# eth_ksz8567r_switch.net
KiCad netlist of a schematic drawn in Altium Designer
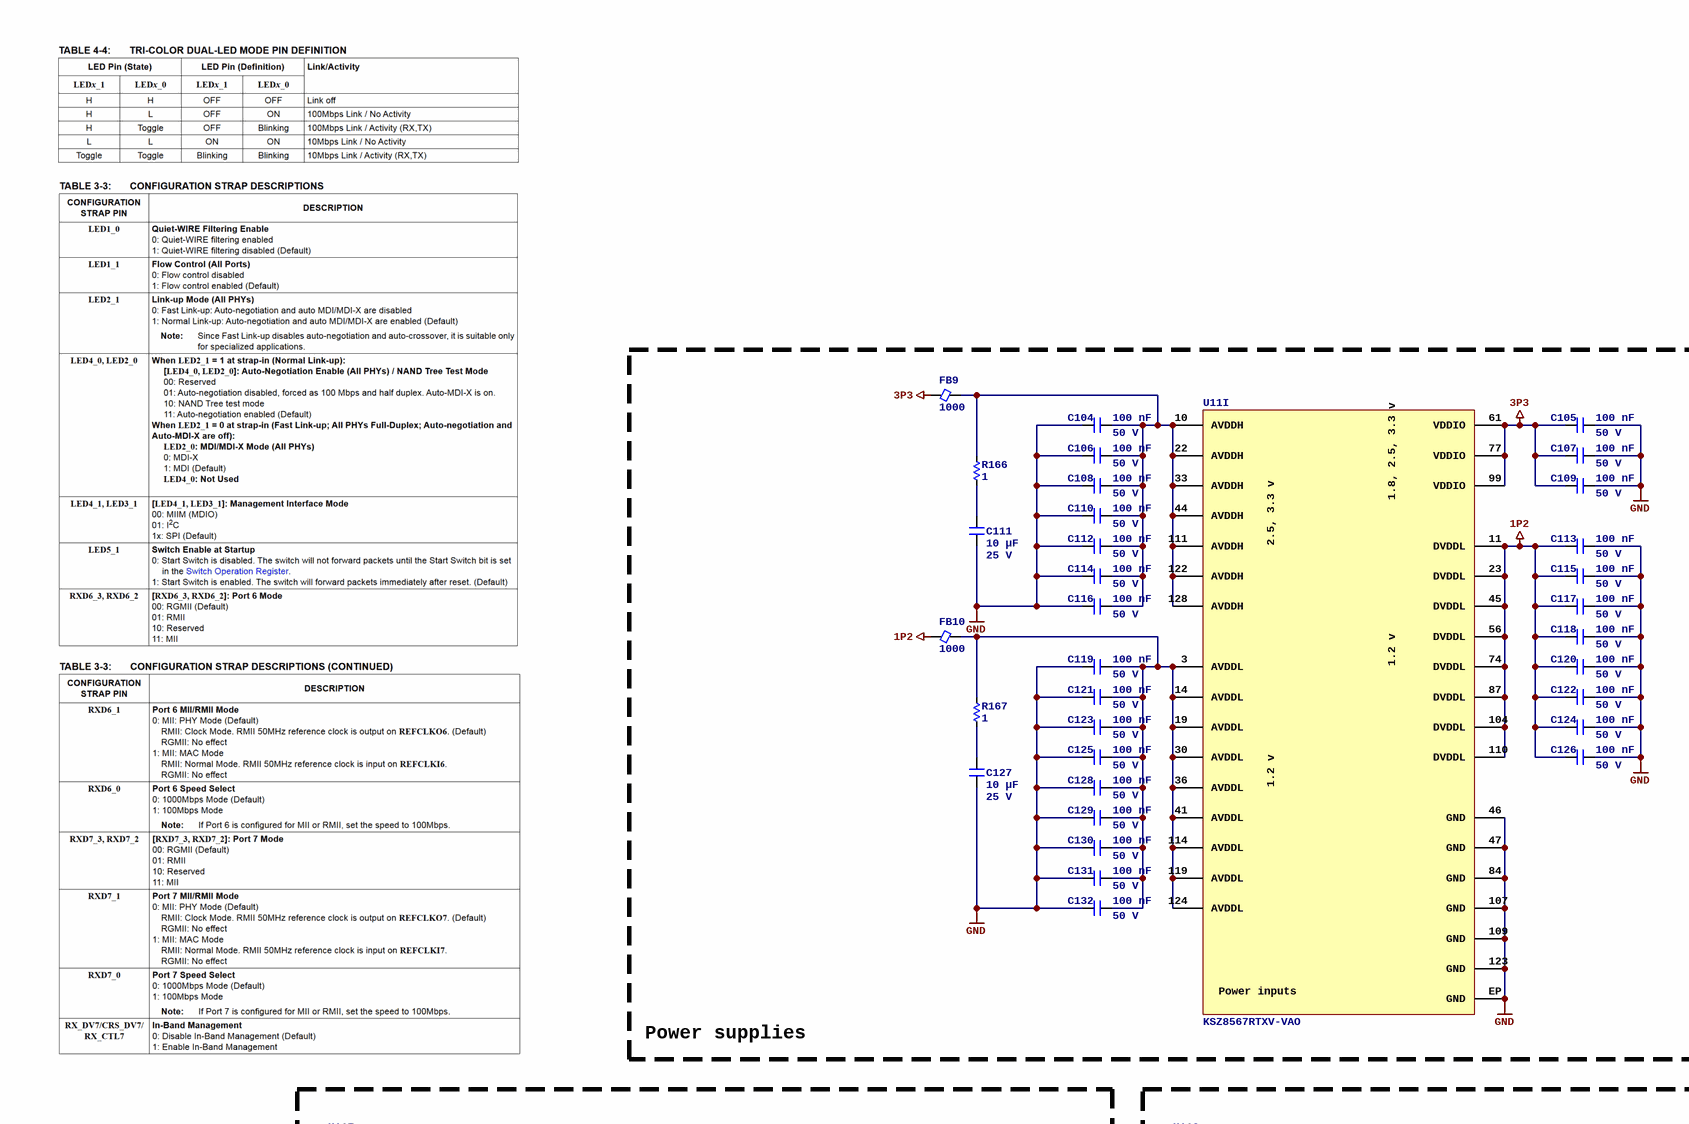
[diagram p0: eth_ksz8567r_switch.SchDoc, top left]
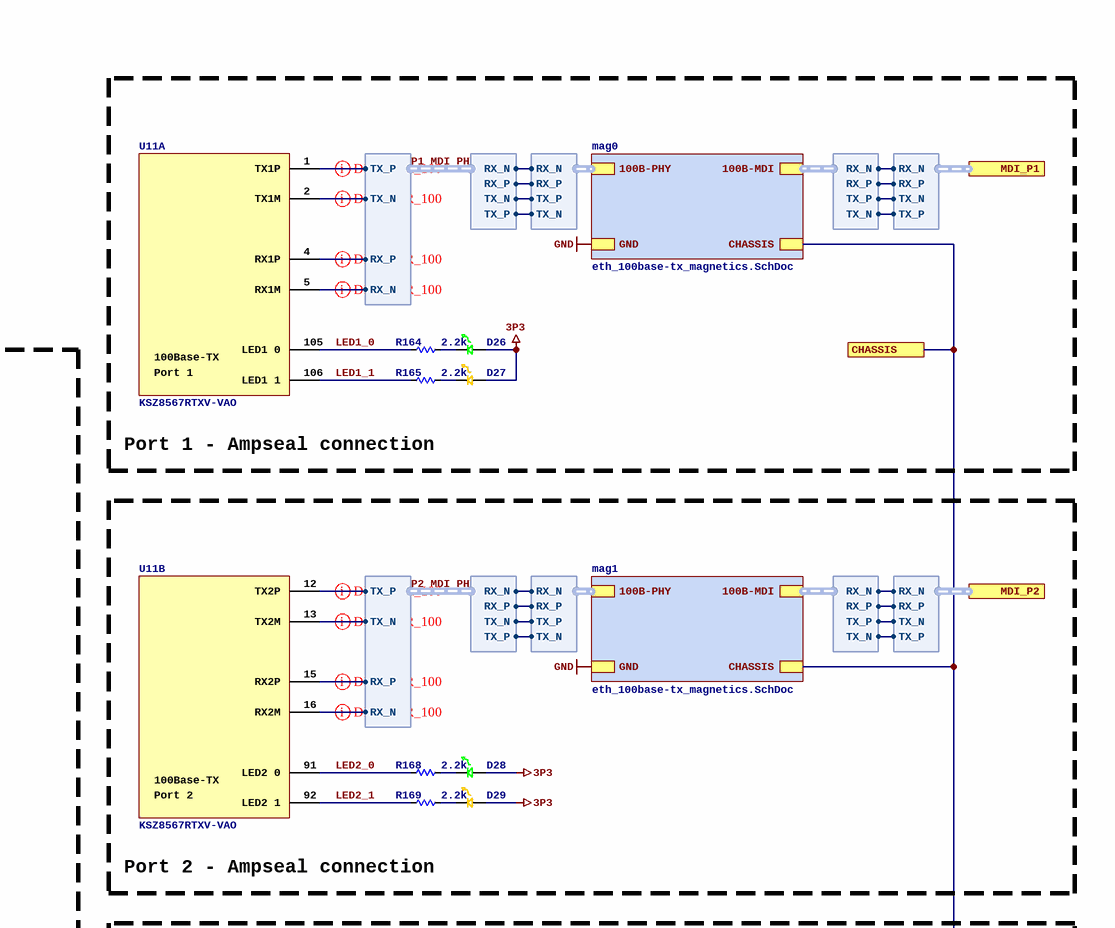
[diagram p1: eth_ksz8567r_switch.SchDoc, top right]
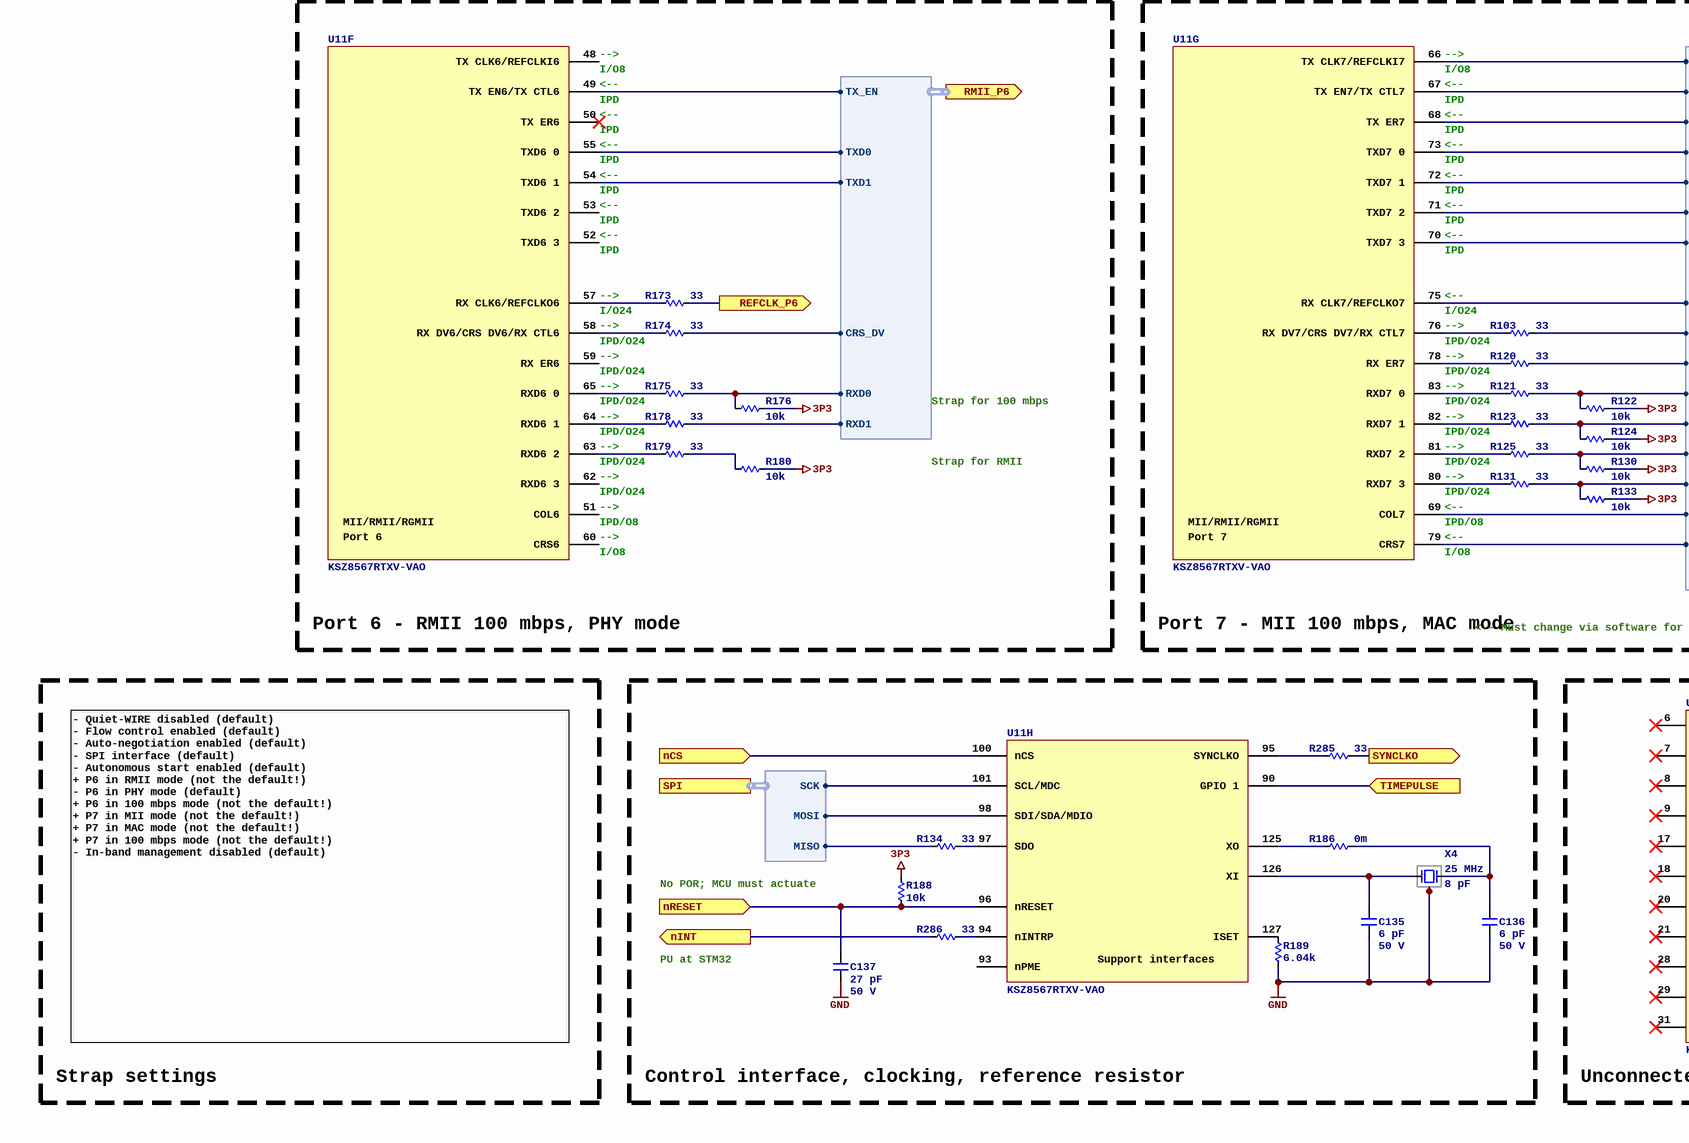
[diagram p2: eth_ksz8567r_switch.SchDoc, bottom left]
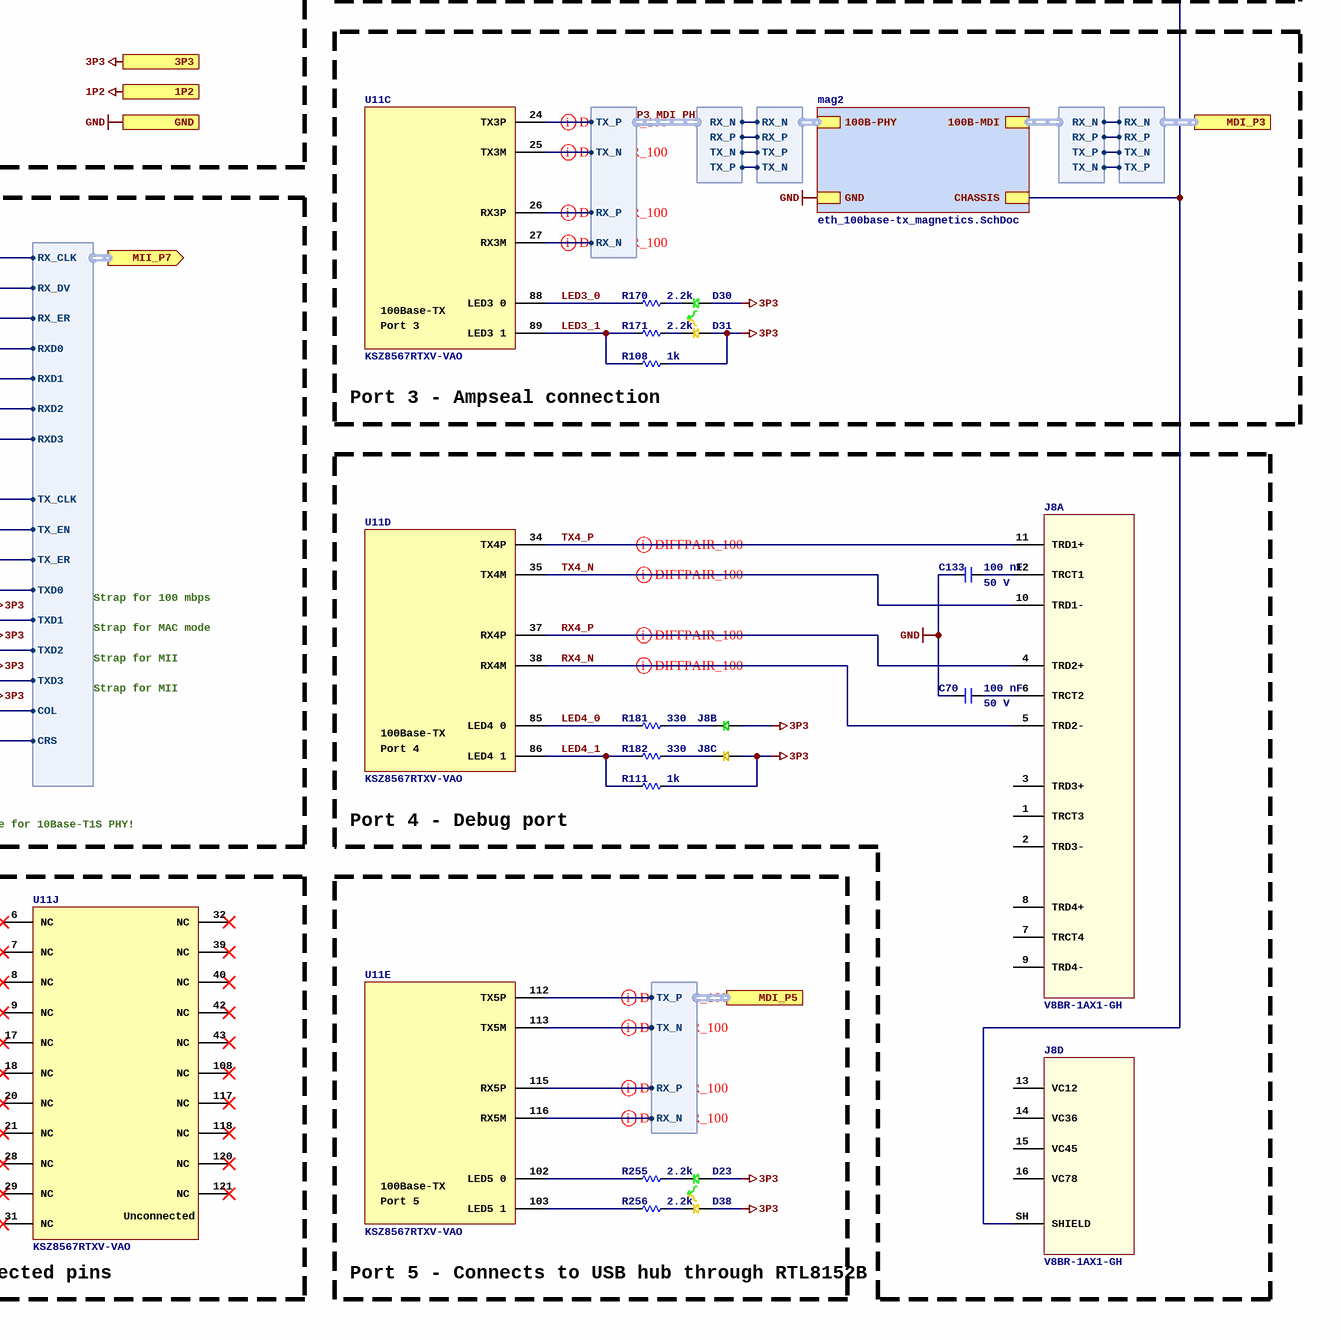
[diagram p3: eth_ksz8567r_switch.SchDoc, bottom right]

(export (version "E")
  (design (tool "Eeschema 10.0.6"))
  (components
    (comp (ref "C70")
      (value "CL05B104KB54PNC")
      (footprint "C0402")
      (fields
        (field (name "CAPACITANCE") "100 nF")
        (field (name "MANUFACTURER") "Samsung Electro-Mechanics")
        (field (name "VOLTAGE RATING") "50 V")
      )
      (libsource (lib "database") (part "__template_cap"))
    )
    (comp (ref "C104")
      (value "CL05B104KB54PNC")
      (footprint "C0402")
      (fields
        (field (name "CAPACITANCE") "100 nF")
        (field (name "MANUFACTURER") "Samsung Electro-Mechanics")
        (field (name "VOLTAGE RATING") "50 V")
      )
      (libsource (lib "database") (part "__template_cap"))
    )
    (comp (ref "C105")
      (value "CL05B104KB54PNC")
      (footprint "C0402")
      (fields
        (field (name "CAPACITANCE") "100 nF")
        (field (name "MANUFACTURER") "Samsung Electro-Mechanics")
        (field (name "VOLTAGE RATING") "50 V")
      )
      (libsource (lib "database") (part "__template_cap"))
    )
    (comp (ref "C106")
      (value "CL05B104KB54PNC")
      (footprint "C0402")
      (fields
        (field (name "CAPACITANCE") "100 nF")
        (field (name "MANUFACTURER") "Samsung Electro-Mechanics")
        (field (name "VOLTAGE RATING") "50 V")
      )
      (libsource (lib "database") (part "__template_cap"))
    )
    (comp (ref "C107")
      (value "CL05B104KB54PNC")
      (footprint "C0402")
      (fields
        (field (name "CAPACITANCE") "100 nF")
        (field (name "MANUFACTURER") "Samsung Electro-Mechanics")
        (field (name "VOLTAGE RATING") "50 V")
      )
      (libsource (lib "database") (part "__template_cap"))
    )
    (comp (ref "C108")
      (value "CL05B104KB54PNC")
      (footprint "C0402")
      (fields
        (field (name "CAPACITANCE") "100 nF")
        (field (name "MANUFACTURER") "Samsung Electro-Mechanics")
        (field (name "VOLTAGE RATING") "50 V")
      )
      (libsource (lib "database") (part "__template_cap"))
    )
    (comp (ref "C109")
      (value "CL05B104KB54PNC")
      (footprint "C0402")
      (fields
        (field (name "CAPACITANCE") "100 nF")
        (field (name "MANUFACTURER") "Samsung Electro-Mechanics")
        (field (name "VOLTAGE RATING") "50 V")
      )
      (libsource (lib "database") (part "__template_cap"))
    )
    (comp (ref "C110")
      (value "CL05B104KB54PNC")
      (footprint "C0402")
      (fields
        (field (name "CAPACITANCE") "100 nF")
        (field (name "MANUFACTURER") "Samsung Electro-Mechanics")
        (field (name "VOLTAGE RATING") "50 V")
      )
      (libsource (lib "database") (part "__template_cap"))
    )
    (comp (ref "C111")
      (value "CL21B106KAYQNNE")
      (footprint "C0805")
      (fields
        (field (name "CAPACITANCE") "10 µF")
        (field (name "MANUFACTURER") "Samsung Electro-Mechanics")
        (field (name "VOLTAGE RATING") "25 V")
      )
      (libsource (lib "database") (part "__template_cap"))
    )
    (comp (ref "C112")
      (value "CL05B104KB54PNC")
      (footprint "C0402")
      (fields
        (field (name "CAPACITANCE") "100 nF")
        (field (name "MANUFACTURER") "Samsung Electro-Mechanics")
        (field (name "VOLTAGE RATING") "50 V")
      )
      (libsource (lib "database") (part "__template_cap"))
    )
    (comp (ref "C113")
      (value "CL05B104KB54PNC")
      (footprint "C0402")
      (fields
        (field (name "CAPACITANCE") "100 nF")
        (field (name "MANUFACTURER") "Samsung Electro-Mechanics")
        (field (name "VOLTAGE RATING") "50 V")
      )
      (libsource (lib "database") (part "__template_cap"))
    )
    (comp (ref "C114")
      (value "CL05B104KB54PNC")
      (footprint "C0402")
      (fields
        (field (name "CAPACITANCE") "100 nF")
        (field (name "MANUFACTURER") "Samsung Electro-Mechanics")
        (field (name "VOLTAGE RATING") "50 V")
      )
      (libsource (lib "database") (part "__template_cap"))
    )
    (comp (ref "C115")
      (value "CL05B104KB54PNC")
      (footprint "C0402")
      (fields
        (field (name "CAPACITANCE") "100 nF")
        (field (name "MANUFACTURER") "Samsung Electro-Mechanics")
        (field (name "VOLTAGE RATING") "50 V")
      )
      (libsource (lib "database") (part "__template_cap"))
    )
    (comp (ref "C116")
      (value "CL05B104KB54PNC")
      (footprint "C0402")
      (fields
        (field (name "CAPACITANCE") "100 nF")
        (field (name "MANUFACTURER") "Samsung Electro-Mechanics")
        (field (name "VOLTAGE RATING") "50 V")
      )
      (libsource (lib "database") (part "__template_cap"))
    )
    (comp (ref "C117")
      (value "CL05B104KB54PNC")
      (footprint "C0402")
      (fields
        (field (name "CAPACITANCE") "100 nF")
        (field (name "MANUFACTURER") "Samsung Electro-Mechanics")
        (field (name "VOLTAGE RATING") "50 V")
      )
      (libsource (lib "database") (part "__template_cap"))
    )
    (comp (ref "C118")
      (value "CL05B104KB54PNC")
      (footprint "C0402")
      (fields
        (field (name "CAPACITANCE") "100 nF")
        (field (name "MANUFACTURER") "Samsung Electro-Mechanics")
        (field (name "VOLTAGE RATING") "50 V")
      )
      (libsource (lib "database") (part "__template_cap"))
    )
    (comp (ref "C119")
      (value "CL05B104KB54PNC")
      (footprint "C0402")
      (fields
        (field (name "CAPACITANCE") "100 nF")
        (field (name "MANUFACTURER") "Samsung Electro-Mechanics")
        (field (name "VOLTAGE RATING") "50 V")
      )
      (libsource (lib "database") (part "__template_cap"))
    )
    (comp (ref "C120")
      (value "CL05B104KB54PNC")
      (footprint "C0402")
      (fields
        (field (name "CAPACITANCE") "100 nF")
        (field (name "MANUFACTURER") "Samsung Electro-Mechanics")
        (field (name "VOLTAGE RATING") "50 V")
      )
      (libsource (lib "database") (part "__template_cap"))
    )
    (comp (ref "C121")
      (value "CL05B104KB54PNC")
      (footprint "C0402")
      (fields
        (field (name "CAPACITANCE") "100 nF")
        (field (name "MANUFACTURER") "Samsung Electro-Mechanics")
        (field (name "VOLTAGE RATING") "50 V")
      )
      (libsource (lib "database") (part "__template_cap"))
    )
    (comp (ref "C122")
      (value "CL05B104KB54PNC")
      (footprint "C0402")
      (fields
        (field (name "CAPACITANCE") "100 nF")
        (field (name "MANUFACTURER") "Samsung Electro-Mechanics")
        (field (name "VOLTAGE RATING") "50 V")
      )
      (libsource (lib "database") (part "__template_cap"))
    )
    (comp (ref "C123")
      (value "CL05B104KB54PNC")
      (footprint "C0402")
      (fields
        (field (name "CAPACITANCE") "100 nF")
        (field (name "MANUFACTURER") "Samsung Electro-Mechanics")
        (field (name "VOLTAGE RATING") "50 V")
      )
      (libsource (lib "database") (part "__template_cap"))
    )
    (comp (ref "C124")
      (value "CL05B104KB54PNC")
      (footprint "C0402")
      (fields
        (field (name "CAPACITANCE") "100 nF")
        (field (name "MANUFACTURER") "Samsung Electro-Mechanics")
        (field (name "VOLTAGE RATING") "50 V")
      )
      (libsource (lib "database") (part "__template_cap"))
    )
    (comp (ref "C125")
      (value "CL05B104KB54PNC")
      (footprint "C0402")
      (fields
        (field (name "CAPACITANCE") "100 nF")
        (field (name "MANUFACTURER") "Samsung Electro-Mechanics")
        (field (name "VOLTAGE RATING") "50 V")
      )
      (libsource (lib "database") (part "__template_cap"))
    )
    (comp (ref "C126")
      (value "CL05B104KB54PNC")
      (footprint "C0402")
      (fields
        (field (name "CAPACITANCE") "100 nF")
        (field (name "MANUFACTURER") "Samsung Electro-Mechanics")
        (field (name "VOLTAGE RATING") "50 V")
      )
      (libsource (lib "database") (part "__template_cap"))
    )
    (comp (ref "C127")
      (value "CL21B106KAYQNNE")
      (footprint "C0805")
      (fields
        (field (name "CAPACITANCE") "10 µF")
        (field (name "MANUFACTURER") "Samsung Electro-Mechanics")
        (field (name "VOLTAGE RATING") "25 V")
      )
      (libsource (lib "database") (part "__template_cap"))
    )
    (comp (ref "C128")
      (value "CL05B104KB54PNC")
      (footprint "C0402")
      (fields
        (field (name "CAPACITANCE") "100 nF")
        (field (name "MANUFACTURER") "Samsung Electro-Mechanics")
        (field (name "VOLTAGE RATING") "50 V")
      )
      (libsource (lib "database") (part "__template_cap"))
    )
    (comp (ref "C129")
      (value "CL05B104KB54PNC")
      (footprint "C0402")
      (fields
        (field (name "CAPACITANCE") "100 nF")
        (field (name "MANUFACTURER") "Samsung Electro-Mechanics")
        (field (name "VOLTAGE RATING") "50 V")
      )
      (libsource (lib "database") (part "__template_cap"))
    )
    (comp (ref "C130")
      (value "CL05B104KB54PNC")
      (footprint "C0402")
      (fields
        (field (name "CAPACITANCE") "100 nF")
        (field (name "MANUFACTURER") "Samsung Electro-Mechanics")
        (field (name "VOLTAGE RATING") "50 V")
      )
      (libsource (lib "database") (part "__template_cap"))
    )
    (comp (ref "C131")
      (value "CL05B104KB54PNC")
      (footprint "C0402")
      (fields
        (field (name "CAPACITANCE") "100 nF")
        (field (name "MANUFACTURER") "Samsung Electro-Mechanics")
        (field (name "VOLTAGE RATING") "50 V")
      )
      (libsource (lib "database") (part "__template_cap"))
    )
    (comp (ref "C132")
      (value "CL05B104KB54PNC")
      (footprint "C0402")
      (fields
        (field (name "CAPACITANCE") "100 nF")
        (field (name "MANUFACTURER") "Samsung Electro-Mechanics")
        (field (name "VOLTAGE RATING") "50 V")
      )
      (libsource (lib "database") (part "__template_cap"))
    )
    (comp (ref "C133")
      (value "CL05B104KB54PNC")
      (footprint "C0402")
      (fields
        (field (name "CAPACITANCE") "100 nF")
        (field (name "MANUFACTURER") "Samsung Electro-Mechanics")
        (field (name "VOLTAGE RATING") "50 V")
      )
      (libsource (lib "database") (part "__template_cap"))
    )
    (comp (ref "C135")
      (value "0402CG6R0C500NT")
      (footprint "C0402")
      (fields
        (field (name "CAPACITANCE") "6 pF")
        (field (name "MANUFACTURER") "FH(Guangdong Fenghua Advanced Tech)")
        (field (name "VOLTAGE RATING") "50 V")
      )
      (libsource (lib "database") (part "__template_cap"))
    )
    (comp (ref "C136")
      (value "0402CG6R0C500NT")
      (footprint "C0402")
      (fields
        (field (name "CAPACITANCE") "6 pF")
        (field (name "MANUFACTURER") "FH(Guangdong Fenghua Advanced Tech)")
        (field (name "VOLTAGE RATING") "50 V")
      )
      (libsource (lib "database") (part "__template_cap"))
    )
    (comp (ref "C137")
      (value "0402CG270J500NT")
      (footprint "C0402")
      (fields
        (field (name "CAPACITANCE") "27 pF")
        (field (name "MANUFACTURER") "FH(Guangdong Fenghua Advanced Tech)")
        (field (name "VOLTAGE RATING") "50 V")
      )
      (libsource (lib "database") (part "__template_cap"))
    )
    (comp (ref "D23")
      (value "LTST-C190GKT")
      (footprint "LED_0603P_GREEN")
      (description "LED GREEN CLEAR 0603 SMD")
      (fields (field (name "MANUFACTURER") "Lite-On Inc"))
      (libsource (lib "") (part "__template_led_green_1"))
    )
    (comp (ref "D26")
      (value "LTST-C190GKT")
      (footprint "LED_0603P_GREEN")
      (description "LED GREEN CLEAR 0603 SMD")
      (fields (field (name "MANUFACTURER") "Lite-On Inc"))
      (libsource (lib "database") (part "__template_led_green"))
    )
    (comp (ref "D27")
      (value "LTST-C190AKT")
      (footprint "LED_0603P_AMBER")
      (description "LED AMBER CLEAR 0603 SMD")
      (fields (field (name "MANUFACTURER") "Lite-On Inc"))
      (libsource (lib "database") (part "__template_led_amber"))
    )
    (comp (ref "D28")
      (value "LTST-C190GKT")
      (footprint "LED_0603P_GREEN")
      (description "LED GREEN CLEAR 0603 SMD")
      (fields (field (name "MANUFACTURER") "Lite-On Inc"))
      (libsource (lib "database") (part "__template_led_green"))
    )
    (comp (ref "D29")
      (value "LTST-C190AKT")
      (footprint "LED_0603P_AMBER")
      (description "LED AMBER CLEAR 0603 SMD")
      (fields (field (name "MANUFACTURER") "Lite-On Inc"))
      (libsource (lib "database") (part "__template_led_amber"))
    )
    (comp (ref "D30")
      (value "LTST-C190GKT")
      (footprint "LED_0603P_GREEN")
      (description "LED GREEN CLEAR 0603 SMD")
      (fields (field (name "MANUFACTURER") "Lite-On Inc"))
      (libsource (lib "") (part "__template_led_green_1"))
    )
    (comp (ref "D31")
      (value "LTST-C190AKT")
      (footprint "LED_0603P_AMBER")
      (description "LED AMBER CLEAR 0603 SMD")
      (fields (field (name "MANUFACTURER") "Lite-On Inc"))
      (libsource (lib "database") (part "__template_led_amber"))
    )
    (comp (ref "D38")
      (value "LTST-C190AKT")
      (footprint "LED_0603P_AMBER")
      (description "LED AMBER CLEAR 0603 SMD")
      (fields (field (name "MANUFACTURER") "Lite-On Inc"))
      (libsource (lib "database") (part "__template_led_amber"))
    )
    (comp (ref "FB9")
      (value "MGGB2012M600HT-LF")
      (footprint "FB0805")
      (fields (field (name "MANUFACTURER") "microgate") (field (name "CURRENT RATING (MA)") "1000"))
      (libsource (lib "database") (part "__template_fb"))
    )
    (comp (ref "FB10")
      (value "MGGB2012M600HT-LF")
      (footprint "FB0805")
      (fields (field (name "MANUFACTURER") "microgate") (field (name "CURRENT RATING (MA)") "1000"))
      (libsource (lib "database") (part "__template_fb"))
    )
    (comp (ref "J8")
      (value "V8BR-1AX1-GH")
      (footprint "BELFUSE_V8BR-1AX1-GH")
      (description "Conn RJ-45 F 8 POS 1.02mm Solder ST Thru-Hole 20 Terminal 1 Port Tray")
      (fields (field (name "MANUFACTURER") "Bel"))
      (libsource (lib "") (part "V8BR-1AX1-GH_1"))
    )
    (comp (ref "R103")
      (value "33")
      (footprint "R0402")
      (fields
        (field (name "TOLERANCE") "1%")
        (field (name "MANUFACTURER PART NUMBER") "0402WGF330JTCE")
        (field (name "MANUFACTURER") "UNI-ROYAL(Uniroyal Elec)")
      )
      (libsource (lib "database") (part "__template_resistor"))
    )
    (comp (ref "R108")
      (value "1k")
      (footprint "R0402")
      (fields
        (field (name "TOLERANCE") "1%")
        (field (name "MANUFACTURER PART NUMBER") "0402WGF1001TCE")
        (field (name "MANUFACTURER") "UNI-ROYAL(Uniroyal Elec)")
      )
      (libsource (lib "database") (part "__template_resistor"))
    )
    (comp (ref "R111")
      (value "1k")
      (footprint "R0402")
      (fields
        (field (name "TOLERANCE") "1%")
        (field (name "MANUFACTURER PART NUMBER") "0402WGF1001TCE")
        (field (name "MANUFACTURER") "UNI-ROYAL(Uniroyal Elec)")
      )
      (libsource (lib "database") (part "__template_resistor"))
    )
    (comp (ref "R120")
      (value "33")
      (footprint "R0402")
      (fields
        (field (name "TOLERANCE") "1%")
        (field (name "MANUFACTURER PART NUMBER") "0402WGF330JTCE")
        (field (name "MANUFACTURER") "UNI-ROYAL(Uniroyal Elec)")
      )
      (libsource (lib "database") (part "__template_resistor"))
    )
    (comp (ref "R121")
      (value "33")
      (footprint "R0402")
      (fields
        (field (name "TOLERANCE") "1%")
        (field (name "MANUFACTURER PART NUMBER") "0402WGF330JTCE")
        (field (name "MANUFACTURER") "UNI-ROYAL(Uniroyal Elec)")
      )
      (libsource (lib "database") (part "__template_resistor"))
    )
    (comp (ref "R122")
      (value "10k")
      (footprint "R0402")
      (fields
        (field (name "TOLERANCE") "1%")
        (field (name "MANUFACTURER PART NUMBER") "0402WGF1002TCE")
        (field (name "MANUFACTURER") "UNI-ROYAL(Uniroyal Elec)")
      )
      (libsource (lib "database") (part "__template_resistor"))
    )
    (comp (ref "R123")
      (value "33")
      (footprint "R0402")
      (fields
        (field (name "TOLERANCE") "1%")
        (field (name "MANUFACTURER PART NUMBER") "0402WGF330JTCE")
        (field (name "MANUFACTURER") "UNI-ROYAL(Uniroyal Elec)")
      )
      (libsource (lib "database") (part "__template_resistor"))
    )
    (comp (ref "R124")
      (value "10k")
      (footprint "R0402")
      (fields
        (field (name "TOLERANCE") "1%")
        (field (name "MANUFACTURER PART NUMBER") "0402WGF1002TCE")
        (field (name "MANUFACTURER") "UNI-ROYAL(Uniroyal Elec)")
      )
      (libsource (lib "database") (part "__template_resistor"))
    )
    (comp (ref "R125")
      (value "33")
      (footprint "R0402")
      (fields
        (field (name "TOLERANCE") "1%")
        (field (name "MANUFACTURER PART NUMBER") "0402WGF330JTCE")
        (field (name "MANUFACTURER") "UNI-ROYAL(Uniroyal Elec)")
      )
      (libsource (lib "database") (part "__template_resistor"))
    )
    (comp (ref "R130")
      (value "10k")
      (footprint "R0402")
      (fields
        (field (name "TOLERANCE") "1%")
        (field (name "MANUFACTURER PART NUMBER") "0402WGF1002TCE")
        (field (name "MANUFACTURER") "UNI-ROYAL(Uniroyal Elec)")
      )
      (libsource (lib "database") (part "__template_resistor"))
    )
    (comp (ref "R131")
      (value "33")
      (footprint "R0402")
      (fields
        (field (name "TOLERANCE") "1%")
        (field (name "MANUFACTURER PART NUMBER") "0402WGF330JTCE")
        (field (name "MANUFACTURER") "UNI-ROYAL(Uniroyal Elec)")
      )
      (libsource (lib "database") (part "__template_resistor"))
    )
    (comp (ref "R133")
      (value "10k")
      (footprint "R0402")
      (fields
        (field (name "TOLERANCE") "1%")
        (field (name "MANUFACTURER PART NUMBER") "0402WGF1002TCE")
        (field (name "MANUFACTURER") "UNI-ROYAL(Uniroyal Elec)")
      )
      (libsource (lib "database") (part "__template_resistor"))
    )
    (comp (ref "R134")
      (value "33")
      (footprint "R0402")
      (fields
        (field (name "TOLERANCE") "1%")
        (field (name "MANUFACTURER PART NUMBER") "0402WGF330JTCE")
        (field (name "MANUFACTURER") "UNI-ROYAL(Uniroyal Elec)")
      )
      (libsource (lib "database") (part "__template_resistor"))
    )
    (comp (ref "R164")
      (value "2.2k")
      (footprint "R0402")
      (fields
        (field (name "TOLERANCE") "1%")
        (field (name "MANUFACTURER PART NUMBER") "0402WGF2201TCE")
        (field (name "MANUFACTURER") "UNI-ROYAL(Uniroyal Elec)")
      )
      (libsource (lib "database") (part "__template_resistor"))
    )
    (comp (ref "R165")
      (value "2.2k")
      (footprint "R0402")
      (fields
        (field (name "TOLERANCE") "1%")
        (field (name "MANUFACTURER PART NUMBER") "0402WGF2201TCE")
        (field (name "MANUFACTURER") "UNI-ROYAL(Uniroyal Elec)")
      )
      (libsource (lib "database") (part "__template_resistor"))
    )
    (comp (ref "R166")
      (value "1")
      (footprint "R0402")
      (fields
        (field (name "TOLERANCE") "1%")
        (field (name "MANUFACTURER PART NUMBER") "CRCW04021R00FKED")
        (field (name "MANUFACTURER") "Vishay Intertech")
      )
      (libsource (lib "database") (part "__template_resistor"))
    )
    (comp (ref "R167")
      (value "1")
      (footprint "R0402")
      (fields
        (field (name "TOLERANCE") "1%")
        (field (name "MANUFACTURER PART NUMBER") "CRCW04021R00FKED")
        (field (name "MANUFACTURER") "Vishay Intertech")
      )
      (libsource (lib "database") (part "__template_resistor"))
    )
    (comp (ref "R168")
      (value "2.2k")
      (footprint "R0402")
      (fields
        (field (name "TOLERANCE") "1%")
        (field (name "MANUFACTURER PART NUMBER") "0402WGF2201TCE")
        (field (name "MANUFACTURER") "UNI-ROYAL(Uniroyal Elec)")
      )
      (libsource (lib "database") (part "__template_resistor"))
    )
    (comp (ref "R169")
      (value "2.2k")
      (footprint "R0402")
      (fields
        (field (name "TOLERANCE") "1%")
        (field (name "MANUFACTURER PART NUMBER") "0402WGF2201TCE")
        (field (name "MANUFACTURER") "UNI-ROYAL(Uniroyal Elec)")
      )
      (libsource (lib "database") (part "__template_resistor"))
    )
    (comp (ref "R170")
      (value "2.2k")
      (footprint "R0402")
      (fields
        (field (name "TOLERANCE") "1%")
        (field (name "MANUFACTURER PART NUMBER") "0402WGF2201TCE")
        (field (name "MANUFACTURER") "UNI-ROYAL(Uniroyal Elec)")
      )
      (libsource (lib "database") (part "__template_resistor"))
    )
    (comp (ref "R171")
      (value "2.2k")
      (footprint "R0402")
      (fields
        (field (name "TOLERANCE") "1%")
        (field (name "MANUFACTURER PART NUMBER") "0402WGF2201TCE")
        (field (name "MANUFACTURER") "UNI-ROYAL(Uniroyal Elec)")
      )
      (libsource (lib "database") (part "__template_resistor"))
    )
    (comp (ref "R173")
      (value "33")
      (footprint "R0402")
      (fields
        (field (name "TOLERANCE") "1%")
        (field (name "MANUFACTURER PART NUMBER") "0402WGF330JTCE")
        (field (name "MANUFACTURER") "UNI-ROYAL(Uniroyal Elec)")
      )
      (libsource (lib "database") (part "__template_resistor"))
    )
    (comp (ref "R174")
      (value "33")
      (footprint "R0402")
      (fields
        (field (name "TOLERANCE") "1%")
        (field (name "MANUFACTURER PART NUMBER") "0402WGF330JTCE")
        (field (name "MANUFACTURER") "UNI-ROYAL(Uniroyal Elec)")
      )
      (libsource (lib "database") (part "__template_resistor"))
    )
    (comp (ref "R175")
      (value "33")
      (footprint "R0402")
      (fields
        (field (name "TOLERANCE") "1%")
        (field (name "MANUFACTURER PART NUMBER") "0402WGF330JTCE")
        (field (name "MANUFACTURER") "UNI-ROYAL(Uniroyal Elec)")
      )
      (libsource (lib "database") (part "__template_resistor"))
    )
    (comp (ref "R176")
      (value "10k")
      (footprint "R0402")
      (fields
        (field (name "TOLERANCE") "1%")
        (field (name "MANUFACTURER PART NUMBER") "0402WGF1002TCE")
        (field (name "MANUFACTURER") "UNI-ROYAL(Uniroyal Elec)")
      )
      (libsource (lib "database") (part "__template_resistor"))
    )
    (comp (ref "R178")
      (value "33")
      (footprint "R0402")
      (fields
        (field (name "TOLERANCE") "1%")
        (field (name "MANUFACTURER PART NUMBER") "0402WGF330JTCE")
        (field (name "MANUFACTURER") "UNI-ROYAL(Uniroyal Elec)")
      )
      (libsource (lib "database") (part "__template_resistor"))
    )
    (comp (ref "R179")
      (value "33")
      (footprint "R0402")
      (fields
        (field (name "TOLERANCE") "1%")
        (field (name "MANUFACTURER PART NUMBER") "0402WGF330JTCE")
        (field (name "MANUFACTURER") "UNI-ROYAL(Uniroyal Elec)")
      )
      (libsource (lib "database") (part "__template_resistor"))
    )
    (comp (ref "R180")
      (value "10k")
      (footprint "R0402")
      (fields
        (field (name "TOLERANCE") "1%")
        (field (name "MANUFACTURER PART NUMBER") "0402WGF1002TCE")
        (field (name "MANUFACTURER") "UNI-ROYAL(Uniroyal Elec)")
      )
      (libsource (lib "database") (part "__template_resistor"))
    )
    (comp (ref "R181")
      (value "330")
      (footprint "R0402")
      (fields
        (field (name "TOLERANCE") "1%")
        (field (name "MANUFACTURER PART NUMBER") "0402WGF3300TCE")
        (field (name "MANUFACTURER") "UNI-ROYAL(Uniroyal Elec)")
      )
      (libsource (lib "database") (part "__template_resistor"))
    )
    (comp (ref "R182")
      (value "330")
      (footprint "R0402")
      (fields
        (field (name "TOLERANCE") "1%")
        (field (name "MANUFACTURER PART NUMBER") "0402WGF3300TCE")
        (field (name "MANUFACTURER") "UNI-ROYAL(Uniroyal Elec)")
      )
      (libsource (lib "database") (part "__template_resistor"))
    )
    (comp (ref "R186")
      (value "0m")
      (footprint "R0402")
      (fields
        (field (name "MANUFACTURER PART NUMBER") "0402WGF0000TCE")
        (field (name "MANUFACTURER") "UNI-ROYAL(Uniroyal Elec)")
      )
      (libsource (lib "database") (part "__template_resistor"))
    )
    (comp (ref "R188")
      (value "10k")
      (footprint "R0402")
      (fields
        (field (name "TOLERANCE") "1%")
        (field (name "MANUFACTURER PART NUMBER") "0402WGF1002TCE")
        (field (name "MANUFACTURER") "UNI-ROYAL(Uniroyal Elec)")
      )
      (libsource (lib "database") (part "__template_resistor"))
    )
    (comp (ref "R189")
      (value "6.04k")
      (footprint "R0402")
      (fields
        (field (name "TOLERANCE") "1%")
        (field (name "MANUFACTURER PART NUMBER") "0402WGF6041TCE")
        (field (name "MANUFACTURER") "UNI-ROYAL(Uniroyal Elec)")
      )
      (libsource (lib "database") (part "__template_resistor"))
    )
    (comp (ref "R255")
      (value "2.2k")
      (footprint "R0402")
      (fields
        (field (name "TOLERANCE") "1%")
        (field (name "MANUFACTURER PART NUMBER") "0402WGF2201TCE")
        (field (name "MANUFACTURER") "UNI-ROYAL(Uniroyal Elec)")
      )
      (libsource (lib "database") (part "__template_resistor"))
    )
    (comp (ref "R256")
      (value "2.2k")
      (footprint "R0402")
      (fields
        (field (name "TOLERANCE") "1%")
        (field (name "MANUFACTURER PART NUMBER") "0402WGF2201TCE")
        (field (name "MANUFACTURER") "UNI-ROYAL(Uniroyal Elec)")
      )
      (libsource (lib "database") (part "__template_resistor"))
    )
    (comp (ref "R285")
      (value "33")
      (footprint "R0402")
      (fields
        (field (name "TOLERANCE") "1%")
        (field (name "MANUFACTURER PART NUMBER") "0402WGF330JTCE")
        (field (name "MANUFACTURER") "UNI-ROYAL(Uniroyal Elec)")
      )
      (libsource (lib "database") (part "__template_resistor"))
    )
    (comp (ref "R286")
      (value "33")
      (footprint "R0402")
      (fields
        (field (name "TOLERANCE") "1%")
        (field (name "MANUFACTURER PART NUMBER") "0402WGF330JTCE")
        (field (name "MANUFACTURER") "UNI-ROYAL(Uniroyal Elec)")
      )
      (libsource (lib "database") (part "__template_resistor"))
    )
    (comp (ref "U11")
      (value "KSZ8567RTXV-VAO")
      (footprint "MICROCHIP_C04-418B_128TQFP_14X14_10X10EP")
      (description "Automotive Ethernet Switch 7 Port 10Mbps/100Mbps 128-Pin TQFP EP Tray")
      (fields (field (name "MANUFACTURER") "Microchip"))
      (libsource (lib "database") (part "KSZ8567RTXV-VAO"))
    )
    (comp (ref "X4")
      (value "ABM11W-25.0000MHZ-8-D1X-T3")
      (footprint "4_SMD_2.0X1.6MM")
      (description "25 MHz ±10ppm Crystal 8pF 50 Ohms 4-SMD, No Lead")
      (fields
        (field (name "MANUFACTURER") "Abracon LLC")
        (field (name "FREQUENCY") "25 MHz")
        (field (name "CAPACITANCE") "8 pF")
      )
      (libsource (lib "database") (part "__template_crystal_4pin"))
    )
  )
  (nets
    (net (code "8") (name "/CHASSIS") (class "Default")
      (node (ref "J8") (pin "SH") (pinfunction "SHIELD_SH") (pintype "passive"))
    )
    (net (code "9") (name "/COL") (class "Default")
      (node (ref "U11") (pin "69") (pinfunction "COL7_69") (pintype "passive"))
    )
    (net (code "10") (name "/CRS") (class "Default")
      (node (ref "U11") (pin "79") (pinfunction "CRS7_79") (pintype "passive"))
    )
    (net (code "11") (name "/CRS_DV") (class "Default") (node (ref "R174") (pin "1") (pintype "passive")))
    (net (code "12") (name "/LED1_0") (class "Default")
      (node (ref "R164") (pin "2") (pintype "passive"))
      (node (ref "U11") (pin "105") (pinfunction "LED1_0_105") (pintype "passive"))
    )
    (net (code "13") (name "/LED1_1") (class "Default")
      (node (ref "R165") (pin "2") (pintype "passive"))
      (node (ref "U11") (pin "106") (pinfunction "LED1_1_106") (pintype "passive"))
    )
    (net (code "14") (name "/LED2_0") (class "Default")
      (node (ref "R168") (pin "2") (pintype "passive"))
      (node (ref "U11") (pin "91") (pinfunction "LED2_0_91") (pintype "passive"))
    )
    (net (code "15") (name "/LED2_1") (class "Default")
      (node (ref "R169") (pin "2") (pintype "passive"))
      (node (ref "U11") (pin "92") (pinfunction "LED2_1_92") (pintype "passive"))
    )
    (net (code "16") (name "/LED3_0") (class "Default")
      (node (ref "R170") (pin "2") (pintype "passive"))
      (node (ref "U11") (pin "88") (pinfunction "LED3_0_88") (pintype "passive"))
    )
    (net (code "17") (name "/LED3_1") (class "Default")
      (node (ref "R108") (pin "2") (pintype "passive"))
      (node (ref "R171") (pin "2") (pintype "passive"))
      (node (ref "U11") (pin "89") (pinfunction "LED3_1_89") (pintype "passive"))
    )
    (net (code "18") (name "/LED4_0") (class "Default")
      (node (ref "R181") (pin "1") (pintype "passive"))
      (node (ref "U11") (pin "85") (pinfunction "LED4_0_85") (pintype "passive"))
    )
    (net (code "19") (name "/LED4_1") (class "Default")
      (node (ref "R111") (pin "2") (pintype "passive"))
      (node (ref "R182") (pin "1") (pintype "passive"))
      (node (ref "U11") (pin "86") (pinfunction "LED4_1_86") (pintype "passive"))
    )
    (net (code "20") (name "/MISO") (class "Default") (node (ref "R134") (pin "2") (pintype "passive")))
    (net (code "21") (name "/MOSI") (class "Default")
      (node (ref "U11") (pin "98") (pinfunction "SDI/SDA/MDIO_98") (pintype "passive"))
    )
    (net (code "25") (name "/REFCLK_P6") (class "Default") (node (ref "R173") (pin "1") (pintype "passive")))
    (net (code "26") (name "/RX4_N") (class "Default")
      (node (ref "J8") (pin "5") (pinfunction "TRD2-_5") (pintype "passive"))
      (node (ref "U11") (pin "38") (pinfunction "RX4M_38") (pintype "passive"))
    )
    (net (code "27") (name "/RX4_P") (class "Default")
      (node (ref "J8") (pin "4") (pinfunction "TRD2+_4") (pintype "passive"))
      (node (ref "U11") (pin "37") (pinfunction "RX4P_37") (pintype "passive"))
    )
    (net (code "28") (name "/RXD2") (class "Default")
      (node (ref "U11") (pin "71") (pinfunction "TXD7_2_71") (pintype "passive"))
    )
    (net (code "29") (name "/RXD3") (class "Default")
      (node (ref "U11") (pin "70") (pinfunction "TXD7_3_70") (pintype "passive"))
    )
    (net (code "30") (name "/RX_CLK") (class "Default")
      (node (ref "U11") (pin "66") (pinfunction "TX_CLK7/REFCLKI7_66") (pintype "passive"))
    )
    (net (code "31") (name "/RX_DV") (class "Default")
      (node (ref "U11") (pin "67") (pinfunction "TX_EN7/TX_CTL7_67") (pintype "passive"))
    )
    (net (code "32") (name "/RX_ER") (class "Default")
      (node (ref "U11") (pin "68") (pinfunction "TX_ER7_68") (pintype "passive"))
    )
    (net (code "33") (name "/SCK") (class "Default")
      (node (ref "U11") (pin "101") (pinfunction "SCL/MDC_101") (pintype "passive"))
    )
    (net (code "34") (name "/SYNCLKO") (class "Default") (node (ref "R285") (pin "1") (pintype "passive")))
    (net (code "35") (name "/TIMEPULSE") (class "Default")
      (node (ref "U11") (pin "90") (pinfunction "GPIO_1_90") (pintype "passive"))
    )
    (net (code "36") (name "/TX4_N") (class "Default")
      (node (ref "J8") (pin "10") (pinfunction "TRD1-_10") (pintype "passive"))
      (node (ref "U11") (pin "35") (pinfunction "TX4M_35") (pintype "passive"))
    )
    (net (code "37") (name "/TX4_P") (class "Default")
      (node (ref "J8") (pin "11") (pinfunction "TRD1+_11") (pintype "passive"))
      (node (ref "U11") (pin "34") (pinfunction "TX4P_34") (pintype "passive"))
    )
    (net (code "38") (name "/TXD2") (class "Default")
      (node (ref "R125") (pin "1") (pintype "passive"))
      (node (ref "R130") (pin "2") (pintype "passive"))
    )
    (net (code "39") (name "/TXD3") (class "Default")
      (node (ref "R131") (pin "1") (pintype "passive"))
      (node (ref "R133") (pin "2") (pintype "passive"))
    )
    (net (code "40") (name "/TX_CLK") (class "Default")
      (node (ref "U11") (pin "75") (pinfunction "RX_CLK7/REFCLKO7_75") (pintype "passive"))
    )
    (net (code "41") (name "/TX_ER") (class "Default") (node (ref "R120") (pin "1") (pintype "passive")))
    (net (code "42") (name "/nCS") (class "Default")
      (node (ref "U11") (pin "100") (pinfunction "nCS_100") (pintype "passive"))
    )
    (net (code "43") (name "/nINT") (class "Default") (node (ref "R286") (pin "2") (pintype "passive")))
    (net (code "44") (name "/nRESET") (class "Default")
      (node (ref "C137") (pin "1") (pintype "passive"))
      (node (ref "R188") (pin "2") (pintype "passive"))
      (node (ref "U11") (pin "96") (pinfunction "nRESET_96") (pintype "passive"))
    )
    (net (code "49") (name "1P2") (class "Default")
      (node (ref "C113") (pin "1") (pintype "passive"))
      (node (ref "C115") (pin "1") (pintype "passive"))
      (node (ref "C117") (pin "1") (pintype "passive"))
      (node (ref "C118") (pin "1") (pintype "passive"))
      (node (ref "C120") (pin "1") (pintype "passive"))
      (node (ref "C122") (pin "1") (pintype "passive"))
      (node (ref "C124") (pin "1") (pintype "passive"))
      (node (ref "C126") (pin "1") (pintype "passive"))
      (node (ref "FB10") (pin "1") (pintype "passive"))
      (node (ref "U11") (pin "104") (pinfunction "DVDDL_104") (pintype "passive"))
      (node (ref "U11") (pin "11") (pinfunction "DVDDL_11") (pintype "passive"))
      (node (ref "U11") (pin "110") (pinfunction "DVDDL_110") (pintype "passive"))
      (node (ref "U11") (pin "23") (pinfunction "DVDDL_23") (pintype "passive"))
      (node (ref "U11") (pin "45") (pinfunction "DVDDL_45") (pintype "passive"))
      (node (ref "U11") (pin "56") (pinfunction "DVDDL_56") (pintype "passive"))
      (node (ref "U11") (pin "74") (pinfunction "DVDDL_74") (pintype "passive"))
      (node (ref "U11") (pin "87") (pinfunction "DVDDL_87") (pintype "passive"))
    )
    (net (code "50") (name "3P3") (class "Default")
      (node (ref "C105") (pin "1") (pintype "passive"))
      (node (ref "C107") (pin "1") (pintype "passive"))
      (node (ref "C109") (pin "1") (pintype "passive"))
      (node (ref "D23") (pin "1") (pintype "passive"))
      (node (ref "D26") (pin "1") (pintype "passive"))
      (node (ref "D27") (pin "1") (pintype "passive"))
      (node (ref "D28") (pin "1") (pintype "passive"))
      (node (ref "D29") (pin "1") (pintype "passive"))
      (node (ref "D30") (pin "1") (pintype "passive"))
      (node (ref "D31") (pin "1") (pintype "passive"))
      (node (ref "D38") (pin "1") (pintype "passive"))
      (node (ref "FB9") (pin "1") (pintype "passive"))
      (node (ref "J8") (pin "18") (pintype "passive"))
      (node (ref "J8") (pin "20") (pintype "passive"))
      (node (ref "R108") (pin "1") (pintype "passive"))
      (node (ref "R111") (pin "1") (pintype "passive"))
      (node (ref "R122") (pin "1") (pintype "passive"))
      (node (ref "R124") (pin "1") (pintype "passive"))
      (node (ref "R130") (pin "1") (pintype "passive"))
      (node (ref "R133") (pin "1") (pintype "passive"))
      (node (ref "R176") (pin "1") (pintype "passive"))
      (node (ref "R180") (pin "1") (pintype "passive"))
      (node (ref "R188") (pin "1") (pintype "passive"))
      (node (ref "U11") (pin "61") (pinfunction "VDDIO_61") (pintype "passive"))
      (node (ref "U11") (pin "77") (pinfunction "VDDIO_77") (pintype "passive"))
      (node (ref "U11") (pin "99") (pinfunction "VDDIO_99") (pintype "passive"))
    )
    (net (code "51") (name "GND") (class "Default")
      (node (ref "C104") (pin "2") (pintype "passive"))
      (node (ref "C105") (pin "2") (pintype "passive"))
      (node (ref "C106") (pin "2") (pintype "passive"))
      (node (ref "C107") (pin "2") (pintype "passive"))
      (node (ref "C108") (pin "2") (pintype "passive"))
      (node (ref "C109") (pin "2") (pintype "passive"))
      (node (ref "C110") (pin "2") (pintype "passive"))
      (node (ref "C111") (pin "2") (pintype "passive"))
      (node (ref "C112") (pin "2") (pintype "passive"))
      (node (ref "C113") (pin "2") (pintype "passive"))
      (node (ref "C114") (pin "2") (pintype "passive"))
      (node (ref "C115") (pin "2") (pintype "passive"))
      (node (ref "C116") (pin "2") (pintype "passive"))
      (node (ref "C117") (pin "2") (pintype "passive"))
      (node (ref "C118") (pin "2") (pintype "passive"))
      (node (ref "C119") (pin "2") (pintype "passive"))
      (node (ref "C120") (pin "2") (pintype "passive"))
      (node (ref "C121") (pin "2") (pintype "passive"))
      (node (ref "C122") (pin "2") (pintype "passive"))
      (node (ref "C123") (pin "2") (pintype "passive"))
      (node (ref "C124") (pin "2") (pintype "passive"))
      (node (ref "C125") (pin "2") (pintype "passive"))
      (node (ref "C126") (pin "2") (pintype "passive"))
      (node (ref "C127") (pin "2") (pintype "passive"))
      (node (ref "C128") (pin "2") (pintype "passive"))
      (node (ref "C129") (pin "2") (pintype "passive"))
      (node (ref "C130") (pin "2") (pintype "passive"))
      (node (ref "C131") (pin "2") (pintype "passive"))
      (node (ref "C132") (pin "2") (pintype "passive"))
      (node (ref "C133") (pin "2") (pintype "passive"))
      (node (ref "C135") (pin "2") (pintype "passive"))
      (node (ref "C136") (pin "2") (pintype "passive"))
      (node (ref "C137") (pin "2") (pintype "passive"))
      (node (ref "C70") (pin "2") (pintype "passive"))
      (node (ref "R189") (pin "2") (pintype "passive"))
      (node (ref "U11") (pin "107") (pinfunction "GND_107") (pintype "passive"))
      (node (ref "U11") (pin "109") (pinfunction "GND_109") (pintype "passive"))
      (node (ref "U11") (pin "123") (pinfunction "GND_123") (pintype "passive"))
      (node (ref "U11") (pin "46") (pinfunction "GND_46") (pintype "passive"))
      (node (ref "U11") (pin "47") (pinfunction "GND_47") (pintype "passive"))
      (node (ref "U11") (pin "84") (pinfunction "GND_84") (pintype "passive"))
      (node (ref "U11") (pin "EP") (pinfunction "GND_EP") (pintype "passive"))
      (node (ref "X4") (pin "2") (pinfunction "2_2") (pintype "passive"))
      (node (ref "X4") (pin "4") (pinfunction "4_4") (pintype "passive"))
    )
    (net (code "52") (name "Net-(C104-Pad1)") (class "Default")
      (node (ref "C104") (pin "1") (pintype "passive"))
      (node (ref "C106") (pin "1") (pintype "passive"))
      (node (ref "C108") (pin "1") (pintype "passive"))
      (node (ref "C110") (pin "1") (pintype "passive"))
      (node (ref "C112") (pin "1") (pintype "passive"))
      (node (ref "C114") (pin "1") (pintype "passive"))
      (node (ref "C116") (pin "1") (pintype "passive"))
      (node (ref "FB9") (pin "2") (pintype "passive"))
      (node (ref "R166") (pin "2") (pintype "passive"))
      (node (ref "U11") (pin "10") (pinfunction "AVDDH_10") (pintype "passive"))
      (node (ref "U11") (pin "111") (pinfunction "AVDDH_111") (pintype "passive"))
      (node (ref "U11") (pin "122") (pinfunction "AVDDH_122") (pintype "passive"))
      (node (ref "U11") (pin "128") (pinfunction "AVDDH_128") (pintype "passive"))
      (node (ref "U11") (pin "22") (pinfunction "AVDDH_22") (pintype "passive"))
      (node (ref "U11") (pin "33") (pinfunction "AVDDH_33") (pintype "passive"))
      (node (ref "U11") (pin "44") (pinfunction "AVDDH_44") (pintype "passive"))
    )
    (net (code "53") (name "Net-(C111-Pad1)") (class "Default")
      (node (ref "C111") (pin "1") (pintype "passive"))
      (node (ref "R166") (pin "1") (pintype "passive"))
    )
    (net (code "54") (name "Net-(C119-Pad1)") (class "Default")
      (node (ref "C119") (pin "1") (pintype "passive"))
      (node (ref "C121") (pin "1") (pintype "passive"))
      (node (ref "C123") (pin "1") (pintype "passive"))
      (node (ref "C125") (pin "1") (pintype "passive"))
      (node (ref "C128") (pin "1") (pintype "passive"))
      (node (ref "C129") (pin "1") (pintype "passive"))
      (node (ref "C130") (pin "1") (pintype "passive"))
      (node (ref "C131") (pin "1") (pintype "passive"))
      (node (ref "C132") (pin "1") (pintype "passive"))
      (node (ref "FB10") (pin "2") (pintype "passive"))
      (node (ref "R167") (pin "2") (pintype "passive"))
      (node (ref "U11") (pin "114") (pinfunction "AVDDL_114") (pintype "passive"))
      (node (ref "U11") (pin "119") (pinfunction "AVDDL_119") (pintype "passive"))
      (node (ref "U11") (pin "124") (pinfunction "AVDDL_124") (pintype "passive"))
      (node (ref "U11") (pin "14") (pinfunction "AVDDL_14") (pintype "passive"))
      (node (ref "U11") (pin "19") (pinfunction "AVDDL_19") (pintype "passive"))
      (node (ref "U11") (pin "3") (pinfunction "AVDDL_3") (pintype "passive"))
      (node (ref "U11") (pin "30") (pinfunction "AVDDL_30") (pintype "passive"))
      (node (ref "U11") (pin "36") (pinfunction "AVDDL_36") (pintype "passive"))
      (node (ref "U11") (pin "41") (pinfunction "AVDDL_41") (pintype "passive"))
    )
    (net (code "55") (name "Net-(C127-Pad1)") (class "Default")
      (node (ref "C127") (pin "1") (pintype "passive"))
      (node (ref "R167") (pin "1") (pintype "passive"))
    )
    (net (code "56") (name "Net-(C136-Pad1)") (class "Default")
      (node (ref "C136") (pin "1") (pintype "passive"))
      (node (ref "R186") (pin "2") (pintype "passive"))
      (node (ref "X4") (pin "3") (pinfunction "3_3") (pintype "passive"))
    )
    (net (code "57") (name "Net-(D23-Pad2)") (class "Default")
      (node (ref "D23") (pin "2") (pintype "passive"))
      (node (ref "R255") (pin "1") (pintype "passive"))
    )
    (net (code "58") (name "Net-(D26-Pad2)") (class "Default")
      (node (ref "D26") (pin "2") (pintype "passive"))
      (node (ref "R164") (pin "1") (pintype "passive"))
    )
    (net (code "59") (name "Net-(D27-Pad2)") (class "Default")
      (node (ref "D27") (pin "2") (pintype "passive"))
      (node (ref "R165") (pin "1") (pintype "passive"))
    )
    (net (code "60") (name "Net-(D28-Pad2)") (class "Default")
      (node (ref "D28") (pin "2") (pintype "passive"))
      (node (ref "R168") (pin "1") (pintype "passive"))
    )
    (net (code "61") (name "Net-(D29-Pad2)") (class "Default")
      (node (ref "D29") (pin "2") (pintype "passive"))
      (node (ref "R169") (pin "1") (pintype "passive"))
    )
    (net (code "62") (name "Net-(D30-Pad2)") (class "Default")
      (node (ref "D30") (pin "2") (pintype "passive"))
      (node (ref "R170") (pin "1") (pintype "passive"))
    )
    (net (code "63") (name "Net-(D31-Pad2)") (class "Default")
      (node (ref "D31") (pin "2") (pintype "passive"))
      (node (ref "R171") (pin "1") (pintype "passive"))
    )
    (net (code "64") (name "Net-(D38-Pad2)") (class "Default")
      (node (ref "D38") (pin "2") (pintype "passive"))
      (node (ref "R256") (pin "1") (pintype "passive"))
    )
    (net (code "65") (name "Net-(J8-Pad17)") (class "Default")
      (node (ref "J8") (pin "17") (pintype "passive"))
      (node (ref "R182") (pin "2") (pintype "passive"))
    )
    (net (code "66") (name "Net-(J8-Pad19)") (class "Default")
      (node (ref "J8") (pin "19") (pintype "passive"))
      (node (ref "R181") (pin "2") (pintype "passive"))
    )
    (net (code "67") (name "Net-(J8A-TRCT1)") (class "Default")
      (node (ref "C133") (pin "1") (pintype "passive"))
      (node (ref "J8") (pin "12") (pinfunction "TRCT1_12") (pintype "passive"))
    )
    (net (code "68") (name "Net-(J8A-TRCT2)") (class "Default")
      (node (ref "C70") (pin "1") (pintype "passive"))
      (node (ref "J8") (pin "6") (pinfunction "TRCT2_6") (pintype "passive"))
    )
    (net (code "69") (name "Net-(R121-Pad1)") (class "Default")
      (node (ref "R121") (pin "1") (pintype "passive"))
      (node (ref "R122") (pin "2") (pintype "passive"))
    )
    (net (code "70") (name "Net-(R123-Pad1)") (class "Default")
      (node (ref "R123") (pin "1") (pintype "passive"))
      (node (ref "R124") (pin "2") (pintype "passive"))
    )
    (net (code "71") (name "Net-(R175-Pad1)") (class "Default")
      (node (ref "R175") (pin "1") (pintype "passive"))
      (node (ref "R176") (pin "2") (pintype "passive"))
    )
    (net (code "72") (name "Net-(R179-Pad1)") (class "Default")
      (node (ref "R179") (pin "1") (pintype "passive"))
      (node (ref "R180") (pin "2") (pintype "passive"))
    )
    (net (code "73") (name "Net-(U11E-LED5_0)") (class "Default")
      (node (ref "R255") (pin "2") (pintype "passive"))
      (node (ref "U11") (pin "102") (pinfunction "LED5_0_102") (pintype "passive"))
    )
    (net (code "74") (name "Net-(U11E-LED5_1)") (class "Default")
      (node (ref "R256") (pin "2") (pintype "passive"))
      (node (ref "U11") (pin "103") (pinfunction "LED5_1_103") (pintype "passive"))
    )
    (net (code "75") (name "Net-(U11F-RXD6_0)") (class "Default")
      (node (ref "R175") (pin "2") (pintype "passive"))
      (node (ref "U11") (pin "65") (pinfunction "RXD6_0_65") (pintype "passive"))
    )
    (net (code "76") (name "Net-(U11F-RXD6_1)") (class "Default")
      (node (ref "R178") (pin "2") (pintype "passive"))
      (node (ref "U11") (pin "64") (pinfunction "RXD6_1_64") (pintype "passive"))
    )
    (net (code "77") (name "Net-(U11F-RXD6_2)") (class "Default")
      (node (ref "R179") (pin "2") (pintype "passive"))
      (node (ref "U11") (pin "63") (pinfunction "RXD6_2_63") (pintype "passive"))
    )
    (net (code "78") (name "Net-(U11F-RX_CLK6{slash}REFCLKO6)") (class "Default")
      (node (ref "R173") (pin "2") (pintype "passive"))
      (node (ref "U11") (pin "57") (pinfunction "RX_CLK6/REFCLKO6_57") (pintype "passive"))
    )
    (net (code "79") (name "Net-(U11F-RX_DV6{slash}CRS_DV6{slash}RX_CTL6)") (class "Default")
      (node (ref "R174") (pin "2") (pintype "passive"))
      (node (ref "U11") (pin "58") (pinfunction "RX_DV6/CRS_DV6/RX_CTL6_58") (pintype "passive"))
    )
    (net (code "80") (name "Net-(U11G-RXD7_0)") (class "Default")
      (node (ref "R121") (pin "2") (pintype "passive"))
      (node (ref "U11") (pin "83") (pinfunction "RXD7_0_83") (pintype "passive"))
    )
    (net (code "81") (name "Net-(U11G-RXD7_1)") (class "Default")
      (node (ref "R123") (pin "2") (pintype "passive"))
      (node (ref "U11") (pin "82") (pinfunction "RXD7_1_82") (pintype "passive"))
    )
    (net (code "82") (name "Net-(U11G-RXD7_2)") (class "Default")
      (node (ref "R125") (pin "2") (pintype "passive"))
      (node (ref "U11") (pin "81") (pinfunction "RXD7_2_81") (pintype "passive"))
    )
    (net (code "83") (name "Net-(U11G-RXD7_3)") (class "Default")
      (node (ref "R131") (pin "2") (pintype "passive"))
      (node (ref "U11") (pin "80") (pinfunction "RXD7_3_80") (pintype "passive"))
    )
    (net (code "84") (name "Net-(U11G-RX_DV7{slash}CRS_DV7{slash}RX_CTL7)") (class "Default")
      (node (ref "R103") (pin "2") (pintype "passive"))
      (node (ref "U11") (pin "76") (pinfunction "RX_DV7/CRS_DV7/RX_CTL7_76") (pintype "passive"))
    )
    (net (code "85") (name "Net-(U11G-RX_ER7)") (class "Default")
      (node (ref "R120") (pin "2") (pintype "passive"))
      (node (ref "U11") (pin "78") (pinfunction "RX_ER7_78") (pintype "passive"))
    )
    (net (code "86") (name "Net-(U11H-ISET)") (class "Default")
      (node (ref "R189") (pin "1") (pintype "passive"))
      (node (ref "U11") (pin "127") (pinfunction "ISET_127") (pintype "passive"))
    )
    (net (code "87") (name "Net-(U11H-SDO)") (class "Default")
      (node (ref "R134") (pin "1") (pintype "passive"))
      (node (ref "U11") (pin "97") (pinfunction "SDO_97") (pintype "passive"))
    )
    (net (code "88") (name "Net-(U11H-SYNCLKO)") (class "Default")
      (node (ref "R285") (pin "2") (pintype "passive"))
      (node (ref "U11") (pin "95") (pinfunction "SYNCLKO_95") (pintype "passive"))
    )
    (net (code "89") (name "Net-(U11H-XI)") (class "Default")
      (node (ref "C135") (pin "1") (pintype "passive"))
      (node (ref "U11") (pin "126") (pinfunction "XI_126") (pintype "passive"))
      (node (ref "X4") (pin "1") (pinfunction "1_1") (pintype "passive"))
    )
    (net (code "90") (name "Net-(U11H-XO)") (class "Default")
      (node (ref "R186") (pin "1") (pintype "passive"))
      (node (ref "U11") (pin "125") (pinfunction "XO_125") (pintype "passive"))
    )
    (net (code "91") (name "Net-(U11H-nINTRP)") (class "Default")
      (node (ref "R286") (pin "1") (pintype "passive"))
      (node (ref "U11") (pin "94") (pinfunction "nINTRP_94") (pintype "passive"))
    )
    (net (code "92") (name "unconnected-(J8A-TRCT3-Pad1)") (class "Default")
      (node (ref "J8") (pin "1") (pinfunction "TRCT3_1") (pintype "passive"))
    )
    (net (code "93") (name "unconnected-(J8A-TRCT4-Pad7)") (class "Default")
      (node (ref "J8") (pin "7") (pinfunction "TRCT4_7") (pintype "passive"))
    )
    (net (code "94") (name "unconnected-(J8A-TRD3+-Pad3)") (class "Default")
      (node (ref "J8") (pin "3") (pinfunction "TRD3+_3") (pintype "passive"))
    )
    (net (code "95") (name "unconnected-(J8A-TRD3--Pad2)") (class "Default")
      (node (ref "J8") (pin "2") (pinfunction "TRD3-_2") (pintype "passive"))
    )
    (net (code "96") (name "unconnected-(J8A-TRD4+-Pad8)") (class "Default")
      (node (ref "J8") (pin "8") (pinfunction "TRD4+_8") (pintype "passive"))
    )
    (net (code "97") (name "unconnected-(J8A-TRD4--Pad9)") (class "Default")
      (node (ref "J8") (pin "9") (pinfunction "TRD4-_9") (pintype "passive"))
    )
    (net (code "98") (name "unconnected-(J8D-VC12-Pad13)") (class "Default")
      (node (ref "J8") (pin "13") (pinfunction "VC12_13") (pintype "passive"))
    )
    (net (code "99") (name "unconnected-(J8D-VC36-Pad14)") (class "Default")
      (node (ref "J8") (pin "14") (pinfunction "VC36_14") (pintype "passive"))
    )
    (net (code "100") (name "unconnected-(J8D-VC45-Pad15)") (class "Default")
      (node (ref "J8") (pin "15") (pinfunction "VC45_15") (pintype "passive"))
    )
    (net (code "101") (name "unconnected-(J8D-VC78-Pad16)") (class "Default")
      (node (ref "J8") (pin "16") (pinfunction "VC78_16") (pintype "passive"))
    )
    (net (code "102") (name "unconnected-(R103-Pad1)") (class "Default")
      (node (ref "R103") (pin "1") (pintype "passive"))
    )
    (net (code "103") (name "unconnected-(R178-Pad1)") (class "Default")
      (node (ref "R178") (pin "1") (pintype "passive"))
    )
    (net (code "104") (name "unconnected-(U11A-RX1M-Pad5)") (class "Default")
      (node (ref "U11") (pin "5") (pinfunction "RX1M_5") (pintype "passive"))
    )
    (net (code "105") (name "unconnected-(U11A-RX1P-Pad4)") (class "Default")
      (node (ref "U11") (pin "4") (pinfunction "RX1P_4") (pintype "passive"))
    )
    (net (code "106") (name "unconnected-(U11A-TX1M-Pad2)") (class "Default")
      (node (ref "U11") (pin "2") (pinfunction "TX1M_2") (pintype "passive"))
    )
    (net (code "107") (name "unconnected-(U11A-TX1P-Pad1)") (class "Default")
      (node (ref "U11") (pin "1") (pinfunction "TX1P_1") (pintype "passive"))
    )
    (net (code "108") (name "unconnected-(U11B-RX2M-Pad16)") (class "Default")
      (node (ref "U11") (pin "16") (pinfunction "RX2M_16") (pintype "passive"))
    )
    (net (code "109") (name "unconnected-(U11B-RX2P-Pad15)") (class "Default")
      (node (ref "U11") (pin "15") (pinfunction "RX2P_15") (pintype "passive"))
    )
    (net (code "110") (name "unconnected-(U11B-TX2M-Pad13)") (class "Default")
      (node (ref "U11") (pin "13") (pinfunction "TX2M_13") (pintype "passive"))
    )
    (net (code "111") (name "unconnected-(U11B-TX2P-Pad12)") (class "Default")
      (node (ref "U11") (pin "12") (pinfunction "TX2P_12") (pintype "passive"))
    )
    (net (code "112") (name "unconnected-(U11C-RX3M-Pad27)") (class "Default")
      (node (ref "U11") (pin "27") (pinfunction "RX3M_27") (pintype "passive"))
    )
    (net (code "113") (name "unconnected-(U11C-RX3P-Pad26)") (class "Default")
      (node (ref "U11") (pin "26") (pinfunction "RX3P_26") (pintype "passive"))
    )
    (net (code "114") (name "unconnected-(U11C-TX3M-Pad25)") (class "Default")
      (node (ref "U11") (pin "25") (pinfunction "TX3M_25") (pintype "passive"))
    )
    (net (code "115") (name "unconnected-(U11C-TX3P-Pad24)") (class "Default")
      (node (ref "U11") (pin "24") (pinfunction "TX3P_24") (pintype "passive"))
    )
    (net (code "116") (name "unconnected-(U11E-RX5M-Pad116)") (class "Default")
      (node (ref "U11") (pin "116") (pinfunction "RX5M_116") (pintype "passive"))
    )
    (net (code "117") (name "unconnected-(U11E-RX5P-Pad115)") (class "Default")
      (node (ref "U11") (pin "115") (pinfunction "RX5P_115") (pintype "passive"))
    )
    (net (code "118") (name "unconnected-(U11E-TX5M-Pad113)") (class "Default")
      (node (ref "U11") (pin "113") (pinfunction "TX5M_113") (pintype "passive"))
    )
    (net (code "119") (name "unconnected-(U11E-TX5P-Pad112)") (class "Default")
      (node (ref "U11") (pin "112") (pinfunction "TX5P_112") (pintype "passive"))
    )
    (net (code "120") (name "unconnected-(U11F-COL6-Pad51)") (class "Default")
      (node (ref "U11") (pin "51") (pinfunction "COL6_51") (pintype "passive"))
    )
    (net (code "121") (name "unconnected-(U11F-CRS6-Pad60)") (class "Default")
      (node (ref "U11") (pin "60") (pinfunction "CRS6_60") (pintype "passive"))
    )
    (net (code "122") (name "unconnected-(U11F-RXD6_3-Pad62)") (class "Default")
      (node (ref "U11") (pin "62") (pinfunction "RXD6_3_62") (pintype "passive"))
    )
    (net (code "123") (name "unconnected-(U11F-RX_ER6-Pad59)") (class "Default")
      (node (ref "U11") (pin "59") (pinfunction "RX_ER6_59") (pintype "passive"))
    )
    (net (code "124") (name "unconnected-(U11F-TXD6_0-Pad55)") (class "Default")
      (node (ref "U11") (pin "55") (pinfunction "TXD6_0_55") (pintype "passive"))
    )
    (net (code "125") (name "unconnected-(U11F-TXD6_1-Pad54)") (class "Default")
      (node (ref "U11") (pin "54") (pinfunction "TXD6_1_54") (pintype "passive"))
    )
    (net (code "126") (name "unconnected-(U11F-TXD6_2-Pad53)") (class "Default")
      (node (ref "U11") (pin "53") (pinfunction "TXD6_2_53") (pintype "passive"))
    )
    (net (code "127") (name "unconnected-(U11F-TXD6_3-Pad52)") (class "Default")
      (node (ref "U11") (pin "52") (pinfunction "TXD6_3_52") (pintype "passive"))
    )
    (net (code "128") (name "unconnected-(U11F-TX_CLK6{slash}REFCLKI6-Pad48)") (class "Default")
      (node (ref "U11") (pin "48") (pinfunction "TX_CLK6/REFCLKI6_48") (pintype "passive"))
    )
    (net (code "129") (name "unconnected-(U11F-TX_EN6{slash}TX_CTL6-Pad49)") (class "Default")
      (node (ref "U11") (pin "49") (pinfunction "TX_EN6/TX_CTL6_49") (pintype "passive"))
    )
    (net (code "130") (name "unconnected-(U11F-TX_ER6-Pad50)") (class "Default")
      (node (ref "U11") (pin "50") (pinfunction "TX_ER6_50") (pintype "passive+no_connect"))
    )
    (net (code "131") (name "unconnected-(U11G-TXD7_0-Pad73)") (class "Default")
      (node (ref "U11") (pin "73") (pinfunction "TXD7_0_73") (pintype "passive"))
    )
    (net (code "132") (name "unconnected-(U11G-TXD7_1-Pad72)") (class "Default")
      (node (ref "U11") (pin "72") (pinfunction "TXD7_1_72") (pintype "passive"))
    )
    (net (code "133") (name "unconnected-(U11H-nPME-Pad93)") (class "Default")
      (node (ref "U11") (pin "93") (pinfunction "nPME_93") (pintype "passive"))
    )
    (net (code "134") (name "unconnected-(U11J-NC-Pad6)") (class "Default")
      (node (ref "U11") (pin "6") (pinfunction "NC_6") (pintype "passive+no_connect"))
    )
    (net (code "135") (name "unconnected-(U11J-NC-Pad7)") (class "Default")
      (node (ref "U11") (pin "7") (pinfunction "NC_7") (pintype "passive+no_connect"))
    )
    (net (code "136") (name "unconnected-(U11J-NC-Pad8)") (class "Default")
      (node (ref "U11") (pin "8") (pinfunction "NC_8") (pintype "passive+no_connect"))
    )
    (net (code "137") (name "unconnected-(U11J-NC-Pad9)") (class "Default")
      (node (ref "U11") (pin "9") (pinfunction "NC_9") (pintype "passive+no_connect"))
    )
    (net (code "138") (name "unconnected-(U11J-NC-Pad17)") (class "Default")
      (node (ref "U11") (pin "17") (pinfunction "NC_17") (pintype "passive+no_connect"))
    )
    (net (code "139") (name "unconnected-(U11J-NC-Pad18)") (class "Default")
      (node (ref "U11") (pin "18") (pinfunction "NC_18") (pintype "passive+no_connect"))
    )
    (net (code "140") (name "unconnected-(U11J-NC-Pad20)") (class "Default")
      (node (ref "U11") (pin "20") (pinfunction "NC_20") (pintype "passive+no_connect"))
    )
    (net (code "141") (name "unconnected-(U11J-NC-Pad21)") (class "Default")
      (node (ref "U11") (pin "21") (pinfunction "NC_21") (pintype "passive+no_connect"))
    )
    (net (code "142") (name "unconnected-(U11J-NC-Pad28)") (class "Default")
      (node (ref "U11") (pin "28") (pinfunction "NC_28") (pintype "passive+no_connect"))
    )
    (net (code "143") (name "unconnected-(U11J-NC-Pad29)") (class "Default")
      (node (ref "U11") (pin "29") (pinfunction "NC_29") (pintype "passive+no_connect"))
    )
    (net (code "144") (name "unconnected-(U11J-NC-Pad31)") (class "Default")
      (node (ref "U11") (pin "31") (pinfunction "NC_31") (pintype "passive+no_connect"))
    )
    (net (code "145") (name "unconnected-(U11J-NC-Pad32)") (class "Default")
      (node (ref "U11") (pin "32") (pinfunction "NC_32") (pintype "passive+no_connect"))
    )
    (net (code "146") (name "unconnected-(U11J-NC-Pad39)") (class "Default")
      (node (ref "U11") (pin "39") (pinfunction "NC_39") (pintype "passive+no_connect"))
    )
    (net (code "147") (name "unconnected-(U11J-NC-Pad40)") (class "Default")
      (node (ref "U11") (pin "40") (pinfunction "NC_40") (pintype "passive+no_connect"))
    )
    (net (code "148") (name "unconnected-(U11J-NC-Pad42)") (class "Default")
      (node (ref "U11") (pin "42") (pinfunction "NC_42") (pintype "passive+no_connect"))
    )
    (net (code "149") (name "unconnected-(U11J-NC-Pad43)") (class "Default")
      (node (ref "U11") (pin "43") (pinfunction "NC_43") (pintype "passive+no_connect"))
    )
    (net (code "150") (name "unconnected-(U11J-NC-Pad108)") (class "Default")
      (node (ref "U11") (pin "108") (pinfunction "NC_108") (pintype "passive+no_connect"))
    )
    (net (code "151") (name "unconnected-(U11J-NC-Pad117)") (class "Default")
      (node (ref "U11") (pin "117") (pinfunction "NC_117") (pintype "passive+no_connect"))
    )
    (net (code "152") (name "unconnected-(U11J-NC-Pad118)") (class "Default")
      (node (ref "U11") (pin "118") (pinfunction "NC_118") (pintype "passive+no_connect"))
    )
    (net (code "153") (name "unconnected-(U11J-NC-Pad120)") (class "Default")
      (node (ref "U11") (pin "120") (pinfunction "NC_120") (pintype "passive+no_connect"))
    )
    (net (code "154") (name "unconnected-(U11J-NC-Pad121)") (class "Default")
      (node (ref "U11") (pin "121") (pinfunction "NC_121") (pintype "passive+no_connect"))
    )
  )
)
